# giri-fu-hw.net
KiCad netlist of a schematic drawn in EAGLE
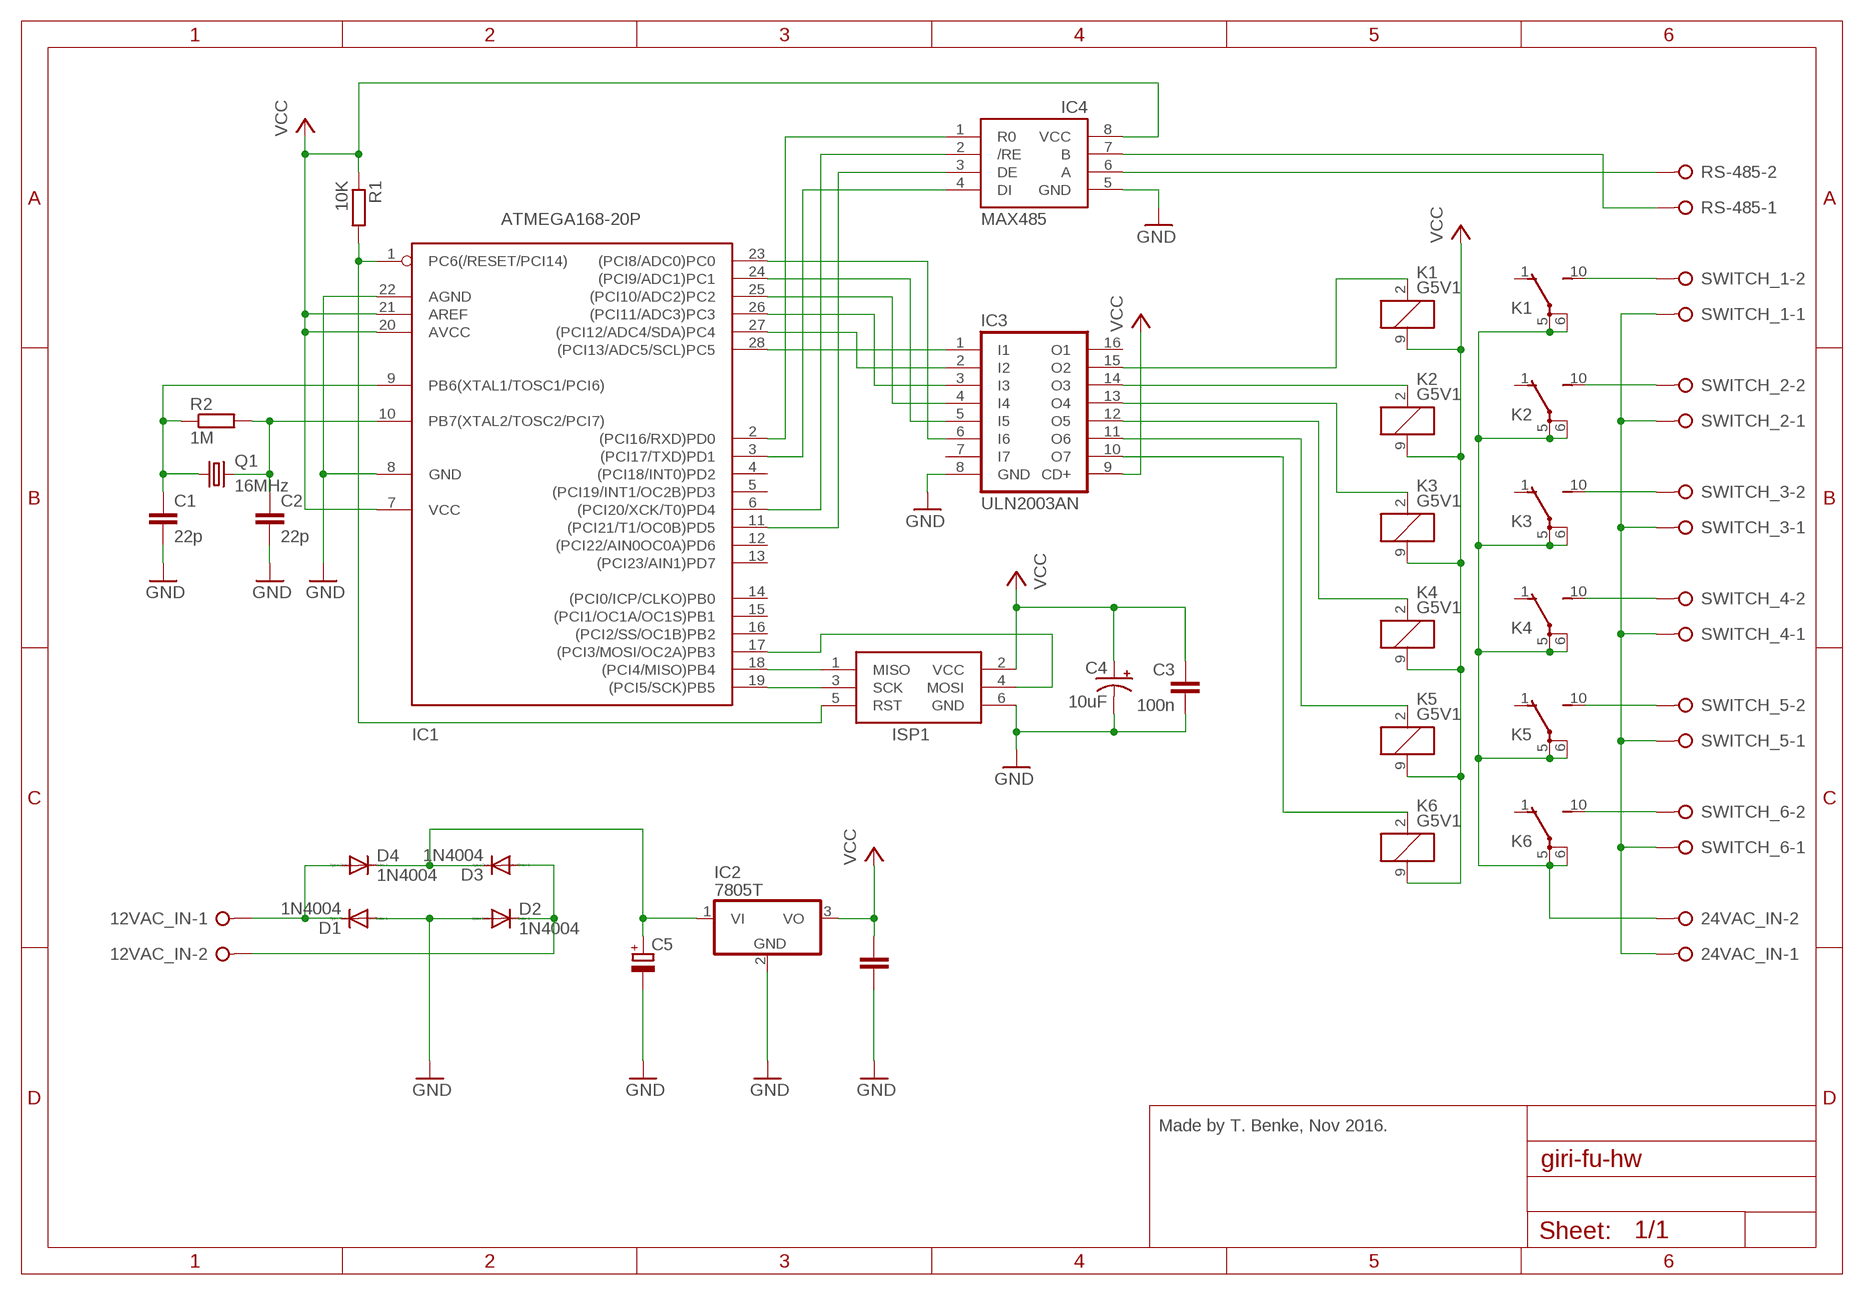
[diagram p0: schematic, sheet 1]

(export (version "E")
  (design (tool "Eeschema 10.0.6"))
  (components
    (comp (ref "12VAC_IN")
      (value "W237-02P")
      (footprint "eagle-import:W237-132")
      (libsource (lib "eagle-import") (part "W237-02P"))
    )
    (comp (ref "24VAC_IN")
      (value "W237-02P")
      (footprint "eagle-import:W237-132")
      (libsource (lib "eagle-import") (part "W237-02P"))
    )
    (comp (ref "C1")
      (value "22p")
      (footprint "eagle-import:C025-025X050")
      (libsource (lib "eagle-import") (part "C-EU025-025X050"))
    )
    (comp (ref "C2")
      (value "22p")
      (footprint "eagle-import:C025-025X050")
      (libsource (lib "eagle-import") (part "C-EU025-025X050"))
    )
    (comp (ref "C3")
      (value "100n")
      (footprint "eagle-import:C025-025X050")
      (libsource (lib "eagle-import") (part "C-EU025-025X050"))
    )
    (comp (ref "C4")
      (value "10uF")
      (footprint "eagle-import:E2-5")
      (libsource (lib "eagle-import") (part "CPOL-USE2-5"))
    )
    (comp (ref "C5")
      (value "CPOL-EUE35-12AXIAL")
      (footprint "eagle-import:E35-12")
      (libsource (lib "eagle-import") (part "CPOL-EUE35-12AXIAL"))
    )
    (comp (ref "D1")
      (value "1N4004")
      (footprint "eagle-import:DO41-10")
      (libsource (lib "eagle-import") (part "1N4004"))
    )
    (comp (ref "D2")
      (value "1N4004")
      (footprint "eagle-import:DO41-10")
      (libsource (lib "eagle-import") (part "1N4004"))
    )
    (comp (ref "D3")
      (value "1N4004")
      (footprint "eagle-import:DO41-10")
      (libsource (lib "eagle-import") (part "1N4004"))
    )
    (comp (ref "D4")
      (value "1N4004")
      (footprint "eagle-import:DO41-10")
      (libsource (lib "eagle-import") (part "1N4004"))
    )
    (comp (ref "IC1")
      (value "ATMEGA168-20P")
      (footprint "eagle-import:DIL28-3")
      (libsource (lib "eagle-import") (part "ATMEGA168P-20"))
    )
    (comp (ref "IC2")
      (value "7805T")
      (footprint "eagle-import:TO220H")
      (libsource (lib "eagle-import") (part "78T05"))
    )
    (comp (ref "IC3")
      (value "ULN2003AN")
      (footprint "eagle-import:DIL16")
      (libsource (lib "eagle-import") (part "ULN2003AN"))
    )
    (comp (ref "IC4")
      (value "MAX485")
      (footprint "eagle-import:DIL08")
      (fields (field (name "MANUFACTURER_PARTNO") "MAX485ECPA+"))
      (libsource (lib "eagle-import") (part "MAX485"))
    )
    (comp (ref "ISP1")
      (value "AVRISP-6")
      (footprint "eagle-import:AVRISP")
      (libsource (lib "eagle-import") (part "AVRISP-6"))
    )
    (comp (ref "K1")
      (value "G5V1")
      (footprint "eagle-import:G5V1")
      (fields (field (name "MPN") "G5V-1-DC24"))
      (libsource (lib "eagle-import") (part "G5V1"))
    )
    (comp (ref "K2")
      (value "G5V1")
      (footprint "eagle-import:G5V1")
      (fields (field (name "MPN") "G5V-1-DC24"))
      (libsource (lib "eagle-import") (part "G5V1"))
    )
    (comp (ref "K3")
      (value "G5V1")
      (footprint "eagle-import:G5V1")
      (fields (field (name "MPN") "G5V-1-DC24"))
      (libsource (lib "eagle-import") (part "G5V1"))
    )
    (comp (ref "K4")
      (value "G5V1")
      (footprint "eagle-import:G5V1")
      (fields (field (name "MPN") "G5V-1-DC24"))
      (libsource (lib "eagle-import") (part "G5V1"))
    )
    (comp (ref "K5")
      (value "G5V1")
      (footprint "eagle-import:G5V1")
      (fields (field (name "MPN") "G5V-1-DC24"))
      (libsource (lib "eagle-import") (part "G5V1"))
    )
    (comp (ref "K6")
      (value "G5V1")
      (footprint "eagle-import:G5V1")
      (fields (field (name "MPN") "G5V-1-DC24"))
      (libsource (lib "eagle-import") (part "G5V1"))
    )
    (comp (ref "Q1")
      (value "16MHz")
      (footprint "eagle-import:HC49U-V")
      (libsource (lib "eagle-import") (part "CRYSTALHC49U-V"))
    )
    (comp (ref "R1")
      (value "10K")
      (footprint "eagle-import:0207_10")
      (libsource (lib "eagle-import") (part "R-EU_0207/10"))
    )
    (comp (ref "R2")
      (value "1M")
      (footprint "eagle-import:0207_10")
      (libsource (lib "eagle-import") (part "R-EU_0207/10"))
    )
    (comp (ref "RS-485")
      (value "W237-02P")
      (footprint "eagle-import:W237-132")
      (libsource (lib "eagle-import") (part "W237-02P"))
    )
    (comp (ref "SWITCH_1")
      (value "W237-02P")
      (footprint "eagle-import:W237-132")
      (libsource (lib "eagle-import") (part "W237-02P"))
    )
    (comp (ref "SWITCH_2")
      (value "W237-02P")
      (footprint "eagle-import:W237-132")
      (libsource (lib "eagle-import") (part "W237-02P"))
    )
    (comp (ref "SWITCH_3")
      (value "W237-02P")
      (footprint "eagle-import:W237-132")
      (libsource (lib "eagle-import") (part "W237-02P"))
    )
    (comp (ref "SWITCH_4")
      (value "W237-02P")
      (footprint "eagle-import:W237-132")
      (libsource (lib "eagle-import") (part "W237-02P"))
    )
    (comp (ref "SWITCH_5")
      (value "W237-02P")
      (footprint "eagle-import:W237-132")
      (libsource (lib "eagle-import") (part "W237-02P"))
    )
    (comp (ref "SWITCH_6")
      (value "W237-02P")
      (footprint "eagle-import:W237-132")
      (libsource (lib "eagle-import") (part "W237-02P"))
    )
  )
  (nets
    (net (code "1") (name "GND") (class "Default")
      (node (ref "C1") (pin "2") (pinfunction "2_2") (pintype "passive"))
      (node (ref "C2") (pin "2") (pinfunction "2_2") (pintype "passive"))
      (node (ref "C3") (pin "2") (pinfunction "2_2") (pintype "passive"))
      (node (ref "C4") (pin "-") (pinfunction "-_-") (pintype "passive"))
      (node (ref "C5") (pin "-") (pinfunction "-_-") (pintype "passive"))
      (node (ref "D1") (pin "A") (pinfunction "A_A") (pintype "passive"))
      (node (ref "D2") (pin "A") (pinfunction "A_A") (pintype "passive"))
      (node (ref "IC1") (pin "22") (pinfunction "AGND_22") (pintype "bidirectional"))
      (node (ref "IC1") (pin "8") (pinfunction "GND_8") (pintype "bidirectional"))
      (node (ref "IC2") (pin "2") (pinfunction "GND_2") (pintype "passive"))
      (node (ref "IC3") (pin "8") (pinfunction "GND_8") (pintype "power_in"))
      (node (ref "IC4") (pin "5") (pinfunction "GND_5") (pintype "power_in"))
      (node (ref "ISP1") (pin "6") (pinfunction "GND_6") (pintype "power_in"))
    )
    (net (code "2") (name "Net-(12VAC_INA-KL)") (class "Default")
      (node (ref "12VAC_IN") (pin "1") (pinfunction "KL_1") (pintype "passive"))
      (node (ref "D1") (pin "C") (pinfunction "C_C") (pintype "passive"))
      (node (ref "D4") (pin "A") (pinfunction "A_A") (pintype "passive"))
    )
    (net (code "3") (name "Net-(12VAC_INB-KL)") (class "Default")
      (node (ref "12VAC_IN") (pin "2") (pinfunction "KL_2") (pintype "passive"))
      (node (ref "D2") (pin "C") (pinfunction "C_C") (pintype "passive"))
      (node (ref "D3") (pin "A") (pinfunction "A_A") (pintype "passive"))
    )
    (net (code "4") (name "Net-(24VAC_INA-KL)") (class "Default")
      (node (ref "24VAC_IN") (pin "1") (pinfunction "KL_1") (pintype "passive"))
      (node (ref "SWITCH_1") (pin "1") (pinfunction "KL_1") (pintype "passive"))
      (node (ref "SWITCH_2") (pin "1") (pinfunction "KL_1") (pintype "passive"))
      (node (ref "SWITCH_3") (pin "1") (pinfunction "KL_1") (pintype "passive"))
      (node (ref "SWITCH_4") (pin "1") (pinfunction "KL_1") (pintype "passive"))
      (node (ref "SWITCH_5") (pin "1") (pinfunction "KL_1") (pintype "passive"))
      (node (ref "SWITCH_6") (pin "1") (pinfunction "KL_1") (pintype "passive"))
    )
    (net (code "5") (name "Net-(24VAC_INB-KL)") (class "Default")
      (node (ref "24VAC_IN") (pin "2") (pinfunction "KL_2") (pintype "passive"))
      (node (ref "K1") (pin "5") (pinfunction "P_5") (pintype "passive"))
      (node (ref "K1") (pin "6") (pinfunction "P_6") (pintype "passive"))
      (node (ref "K2") (pin "5") (pinfunction "P_5") (pintype "passive"))
      (node (ref "K2") (pin "6") (pinfunction "P_6") (pintype "passive"))
      (node (ref "K3") (pin "5") (pinfunction "P_5") (pintype "passive"))
      (node (ref "K3") (pin "6") (pinfunction "P_6") (pintype "passive"))
      (node (ref "K4") (pin "5") (pinfunction "P_5") (pintype "passive"))
      (node (ref "K4") (pin "6") (pinfunction "P_6") (pintype "passive"))
      (node (ref "K5") (pin "5") (pinfunction "P_5") (pintype "passive"))
      (node (ref "K5") (pin "6") (pinfunction "P_6") (pintype "passive"))
      (node (ref "K6") (pin "5") (pinfunction "P_5") (pintype "passive"))
      (node (ref "K6") (pin "6") (pinfunction "P_6") (pintype "passive"))
    )
    (net (code "6") (name "Net-(IC1-(PCI3{slash}MOSI{slash}OC2A)PB3)") (class "Default")
      (node (ref "IC1") (pin "17") (pinfunction "(PCI3/MOSI/OC2A)PB3_17") (pintype "bidirectional"))
      (node (ref "ISP1") (pin "4") (pinfunction "MOSI_4") (pintype "output"))
    )
    (net (code "7") (name "Net-(IC1-(PCI4{slash}MISO)PB4)") (class "Default")
      (node (ref "IC1") (pin "18") (pinfunction "(PCI4/MISO)PB4_18") (pintype "bidirectional"))
      (node (ref "ISP1") (pin "1") (pinfunction "MISO_1") (pintype "input"))
    )
    (net (code "8") (name "Net-(IC1-(PCI5{slash}SCK)PB5)") (class "Default")
      (node (ref "IC1") (pin "19") (pinfunction "(PCI5/SCK)PB5_19") (pintype "bidirectional"))
      (node (ref "ISP1") (pin "3") (pinfunction "SCK_3") (pintype "output"))
    )
    (net (code "9") (name "Net-(IC1-(PCI8{slash}ADC0)PC0)") (class "Default")
      (node (ref "IC1") (pin "23") (pinfunction "(PCI8/ADC0)PC0_23") (pintype "bidirectional"))
      (node (ref "IC3") (pin "6") (pinfunction "I6_6") (pintype "input"))
    )
    (net (code "10") (name "Net-(IC1-(PCI9{slash}ADC1)PC1)") (class "Default")
      (node (ref "IC1") (pin "24") (pinfunction "(PCI9/ADC1)PC1_24") (pintype "bidirectional"))
      (node (ref "IC3") (pin "5") (pinfunction "I5_5") (pintype "input"))
    )
    (net (code "11") (name "Net-(IC1-(PCI10{slash}ADC2)PC2)") (class "Default")
      (node (ref "IC1") (pin "25") (pinfunction "(PCI10/ADC2)PC2_25") (pintype "bidirectional"))
      (node (ref "IC3") (pin "4") (pinfunction "I4_4") (pintype "input"))
    )
    (net (code "12") (name "Net-(IC1-(PCI11{slash}ADC3)PC3)") (class "Default")
      (node (ref "IC1") (pin "26") (pinfunction "(PCI11/ADC3)PC3_26") (pintype "bidirectional"))
      (node (ref "IC3") (pin "3") (pinfunction "I3_3") (pintype "input"))
    )
    (net (code "13") (name "Net-(IC1-(PCI12{slash}ADC4{slash}SDA)PC4)") (class "Default")
      (node (ref "IC1") (pin "27") (pinfunction "(PCI12/ADC4/SDA)PC4_27") (pintype "bidirectional"))
      (node (ref "IC3") (pin "2") (pinfunction "I2_2") (pintype "input"))
    )
    (net (code "14") (name "Net-(IC1-(PCI13{slash}ADC5{slash}SCL)PC5)") (class "Default")
      (node (ref "IC1") (pin "28") (pinfunction "(PCI13/ADC5/SCL)PC5_28") (pintype "bidirectional"))
      (node (ref "IC3") (pin "1") (pinfunction "I1_1") (pintype "input"))
    )
    (net (code "15") (name "Net-(IC1-(PCI16{slash}RXD)PD0)") (class "Default")
      (node (ref "IC1") (pin "2") (pinfunction "(PCI16/RXD)PD0_2") (pintype "bidirectional"))
      (node (ref "IC4") (pin "1") (pinfunction "R0_1") (pintype "output"))
    )
    (net (code "16") (name "Net-(IC1-(PCI17{slash}TXD)PD1)") (class "Default")
      (node (ref "IC1") (pin "3") (pinfunction "(PCI17/TXD)PD1_3") (pintype "bidirectional"))
      (node (ref "IC4") (pin "4") (pinfunction "DI_4") (pintype "input"))
    )
    (net (code "17") (name "Net-(IC1-(PCI20{slash}XCK{slash}T0)PD4)") (class "Default")
      (node (ref "IC1") (pin "6") (pinfunction "(PCI20/XCK/T0)PD4_6") (pintype "bidirectional"))
      (node (ref "IC4") (pin "2") (pinfunction "/RE_2") (pintype "input"))
    )
    (net (code "18") (name "Net-(IC1-(PCI21{slash}T1{slash}OC0B)PD5)") (class "Default")
      (node (ref "IC1") (pin "11") (pinfunction "(PCI21/T1/OC0B)PD5_11") (pintype "bidirectional"))
      (node (ref "IC4") (pin "3") (pinfunction "DE_3") (pintype "bidirectional"))
    )
    (net (code "19") (name "Net-(IC1-PB6(XTAL1{slash}TOSC1{slash}PCI6))") (class "Default")
      (node (ref "C1") (pin "1") (pinfunction "1_1") (pintype "passive"))
      (node (ref "IC1") (pin "9") (pinfunction "PB6(XTAL1/TOSC1/PCI6)_9") (pintype "bidirectional"))
      (node (ref "Q1") (pin "1") (pinfunction "1_1") (pintype "passive"))
      (node (ref "R2") (pin "1") (pinfunction "1_1") (pintype "passive"))
    )
    (net (code "20") (name "Net-(IC1-PB7(XTAL2{slash}TOSC2{slash}PCI7))") (class "Default")
      (node (ref "C2") (pin "1") (pinfunction "1_1") (pintype "passive"))
      (node (ref "IC1") (pin "10") (pinfunction "PB7(XTAL2/TOSC2/PCI7)_10") (pintype "bidirectional"))
      (node (ref "Q1") (pin "2") (pinfunction "2_2") (pintype "passive"))
      (node (ref "R2") (pin "2") (pinfunction "2_2") (pintype "passive"))
    )
    (net (code "21") (name "Net-(IC1-PC6({slash}RESET{slash}PCI14))") (class "Default")
      (node (ref "IC1") (pin "1") (pinfunction "PC6(/RESET/PCI14)_1") (pintype "bidirectional"))
      (node (ref "ISP1") (pin "5") (pinfunction "RST_5") (pintype "output"))
      (node (ref "R1") (pin "2") (pinfunction "2_2") (pintype "passive"))
    )
    (net (code "22") (name "Net-(IC2-VI)") (class "Default")
      (node (ref "C5") (pin "+") (pinfunction "+_+") (pintype "passive"))
      (node (ref "D3") (pin "C") (pinfunction "C_C") (pintype "passive"))
      (node (ref "D4") (pin "C") (pinfunction "C_C") (pintype "passive"))
      (node (ref "IC2") (pin "1") (pinfunction "VI_1") (pintype "input"))
    )
    (net (code "23") (name "Net-(IC3-O2)") (class "Default")
      (node (ref "IC3") (pin "15") (pinfunction "O2_15") (pintype "open_collector"))
      (node (ref "K1") (pin "2") (pinfunction "1_2") (pintype "passive"))
    )
    (net (code "24") (name "Net-(IC3-O3)") (class "Default")
      (node (ref "IC3") (pin "14") (pinfunction "O3_14") (pintype "open_collector"))
      (node (ref "K2") (pin "2") (pinfunction "1_2") (pintype "passive"))
    )
    (net (code "25") (name "Net-(IC3-O4)") (class "Default")
      (node (ref "IC3") (pin "13") (pinfunction "O4_13") (pintype "open_collector"))
      (node (ref "K3") (pin "2") (pinfunction "1_2") (pintype "passive"))
    )
    (net (code "26") (name "Net-(IC3-O5)") (class "Default")
      (node (ref "IC3") (pin "12") (pinfunction "O5_12") (pintype "open_collector"))
      (node (ref "K4") (pin "2") (pinfunction "1_2") (pintype "passive"))
    )
    (net (code "27") (name "Net-(IC3-O6)") (class "Default")
      (node (ref "IC3") (pin "11") (pinfunction "O6_11") (pintype "open_collector"))
      (node (ref "K5") (pin "2") (pinfunction "1_2") (pintype "passive"))
    )
    (net (code "28") (name "Net-(IC3-O7)") (class "Default")
      (node (ref "IC3") (pin "10") (pinfunction "O7_10") (pintype "open_collector"))
      (node (ref "K6") (pin "2") (pinfunction "1_2") (pintype "passive"))
    )
    (net (code "29") (name "Net-(IC4-A)") (class "Default")
      (node (ref "IC4") (pin "6") (pinfunction "A_6") (pintype "bidirectional"))
      (node (ref "RS-485") (pin "2") (pinfunction "KL_2") (pintype "passive"))
    )
    (net (code "30") (name "Net-(IC4-B)") (class "Default")
      (node (ref "IC4") (pin "7") (pinfunction "B_7") (pintype "bidirectional"))
      (node (ref "RS-485") (pin "1") (pinfunction "KL_1") (pintype "passive"))
    )
    (net (code "31") (name "Net-(K1B-S)") (class "Default")
      (node (ref "K1") (pin "10") (pinfunction "S_10") (pintype "passive"))
      (node (ref "SWITCH_1") (pin "2") (pinfunction "KL_2") (pintype "passive"))
    )
    (net (code "32") (name "Net-(K2B-S)") (class "Default")
      (node (ref "K2") (pin "10") (pinfunction "S_10") (pintype "passive"))
      (node (ref "SWITCH_2") (pin "2") (pinfunction "KL_2") (pintype "passive"))
    )
    (net (code "33") (name "Net-(K3B-S)") (class "Default")
      (node (ref "K3") (pin "10") (pinfunction "S_10") (pintype "passive"))
      (node (ref "SWITCH_3") (pin "2") (pinfunction "KL_2") (pintype "passive"))
    )
    (net (code "34") (name "Net-(K4B-S)") (class "Default")
      (node (ref "K4") (pin "10") (pinfunction "S_10") (pintype "passive"))
      (node (ref "SWITCH_4") (pin "2") (pinfunction "KL_2") (pintype "passive"))
    )
    (net (code "35") (name "Net-(K5B-S)") (class "Default")
      (node (ref "K5") (pin "10") (pinfunction "S_10") (pintype "passive"))
      (node (ref "SWITCH_5") (pin "2") (pinfunction "KL_2") (pintype "passive"))
    )
    (net (code "36") (name "Net-(K6B-S)") (class "Default")
      (node (ref "K6") (pin "10") (pinfunction "S_10") (pintype "passive"))
      (node (ref "SWITCH_6") (pin "2") (pinfunction "KL_2") (pintype "passive"))
    )
    (net (code "37") (name "VCC") (class "Default")
      (node (ref "C3") (pin "1") (pinfunction "1_1") (pintype "passive"))
      (node (ref "C4") (pin "+") (pinfunction "+_+") (pintype "passive"))
      (node (ref "IC1") (pin "20") (pinfunction "AVCC_20") (pintype "bidirectional"))
      (node (ref "IC1") (pin "21") (pinfunction "AREF_21") (pintype "bidirectional"))
      (node (ref "IC1") (pin "7") (pinfunction "VCC_7") (pintype "bidirectional"))
      (node (ref "IC2") (pin "3") (pinfunction "VO_3") (pintype "passive"))
      (node (ref "IC3") (pin "9") (pinfunction "CD+_9") (pintype "passive"))
      (node (ref "IC4") (pin "8") (pinfunction "VCC_8") (pintype "power_in"))
      (node (ref "ISP1") (pin "2") (pinfunction "VCC_2") (pintype "power_in"))
      (node (ref "K1") (pin "9") (pinfunction "2_9") (pintype "passive"))
      (node (ref "K2") (pin "9") (pinfunction "2_9") (pintype "passive"))
      (node (ref "K3") (pin "9") (pinfunction "2_9") (pintype "passive"))
      (node (ref "K4") (pin "9") (pinfunction "2_9") (pintype "passive"))
      (node (ref "K5") (pin "9") (pinfunction "2_9") (pintype "passive"))
      (node (ref "K6") (pin "9") (pinfunction "2_9") (pintype "passive"))
      (node (ref "R1") (pin "1") (pinfunction "1_1") (pintype "passive"))
    )
    (net (code "38") (name "unconnected-(IC1-(PCI0{slash}ICP{slash}CLKO)PB0-Pad14)") (class "Default")
      (node (ref "IC1") (pin "14") (pinfunction "(PCI0/ICP/CLKO)PB0_14") (pintype "bidirectional"))
    )
    (net (code "39") (name "unconnected-(IC1-(PCI1{slash}OC1A{slash}OC1S)PB1-Pad15)") (class "Default")
      (node (ref "IC1") (pin "15") (pinfunction "(PCI1/OC1A/OC1S)PB1_15") (pintype "bidirectional"))
    )
    (net (code "40") (name "unconnected-(IC1-(PCI2{slash}SS{slash}OC1B)PB2-Pad16)") (class "Default")
      (node (ref "IC1") (pin "16") (pinfunction "(PCI2/SS/OC1B)PB2_16") (pintype "bidirectional"))
    )
    (net (code "41") (name "unconnected-(IC1-(PCI18{slash}INT0)PD2-Pad4)") (class "Default")
      (node (ref "IC1") (pin "4") (pinfunction "(PCI18/INT0)PD2_4") (pintype "bidirectional"))
    )
    (net (code "42") (name "unconnected-(IC1-(PCI19{slash}INT1{slash}OC2B)PD3-Pad5)") (class "Default")
      (node (ref "IC1") (pin "5") (pinfunction "(PCI19/INT1/OC2B)PD3_5") (pintype "bidirectional"))
    )
    (net (code "43") (name "unconnected-(IC1-(PCI22{slash}AIN0OC0A)PD6-Pad12)") (class "Default")
      (node (ref "IC1") (pin "12") (pinfunction "(PCI22/AIN0OC0A)PD6_12") (pintype "bidirectional"))
    )
    (net (code "44") (name "unconnected-(IC1-(PCI23{slash}AIN1)PD7-Pad13)") (class "Default")
      (node (ref "IC1") (pin "13") (pinfunction "(PCI23/AIN1)PD7_13") (pintype "bidirectional"))
    )
    (net (code "45") (name "unconnected-(IC3-I7-Pad7)") (class "Default")
      (node (ref "IC3") (pin "7") (pinfunction "I7_7") (pintype "input"))
    )
    (net (code "46") (name "unconnected-(IC3-O1-Pad16)") (class "Default")
      (node (ref "IC3") (pin "16") (pinfunction "O1_16") (pintype "open_collector"))
    )
    (net (code "47") (name "unconnected-(K1B-O-Pad1)") (class "Default")
      (node (ref "K1") (pin "1") (pinfunction "O_1") (pintype "passive"))
    )
    (net (code "48") (name "unconnected-(K2B-O-Pad1)") (class "Default")
      (node (ref "K2") (pin "1") (pinfunction "O_1") (pintype "passive"))
    )
    (net (code "49") (name "unconnected-(K3B-O-Pad1)") (class "Default")
      (node (ref "K3") (pin "1") (pinfunction "O_1") (pintype "passive"))
    )
    (net (code "50") (name "unconnected-(K4B-O-Pad1)") (class "Default")
      (node (ref "K4") (pin "1") (pinfunction "O_1") (pintype "passive"))
    )
    (net (code "51") (name "unconnected-(K5B-O-Pad1)") (class "Default")
      (node (ref "K5") (pin "1") (pinfunction "O_1") (pintype "passive"))
    )
    (net (code "52") (name "unconnected-(K6B-O-Pad1)") (class "Default")
      (node (ref "K6") (pin "1") (pinfunction "O_1") (pintype "passive"))
    )
  )
)
